# payload2.net
KiCad netlist of a schematic drawn in EAGLE
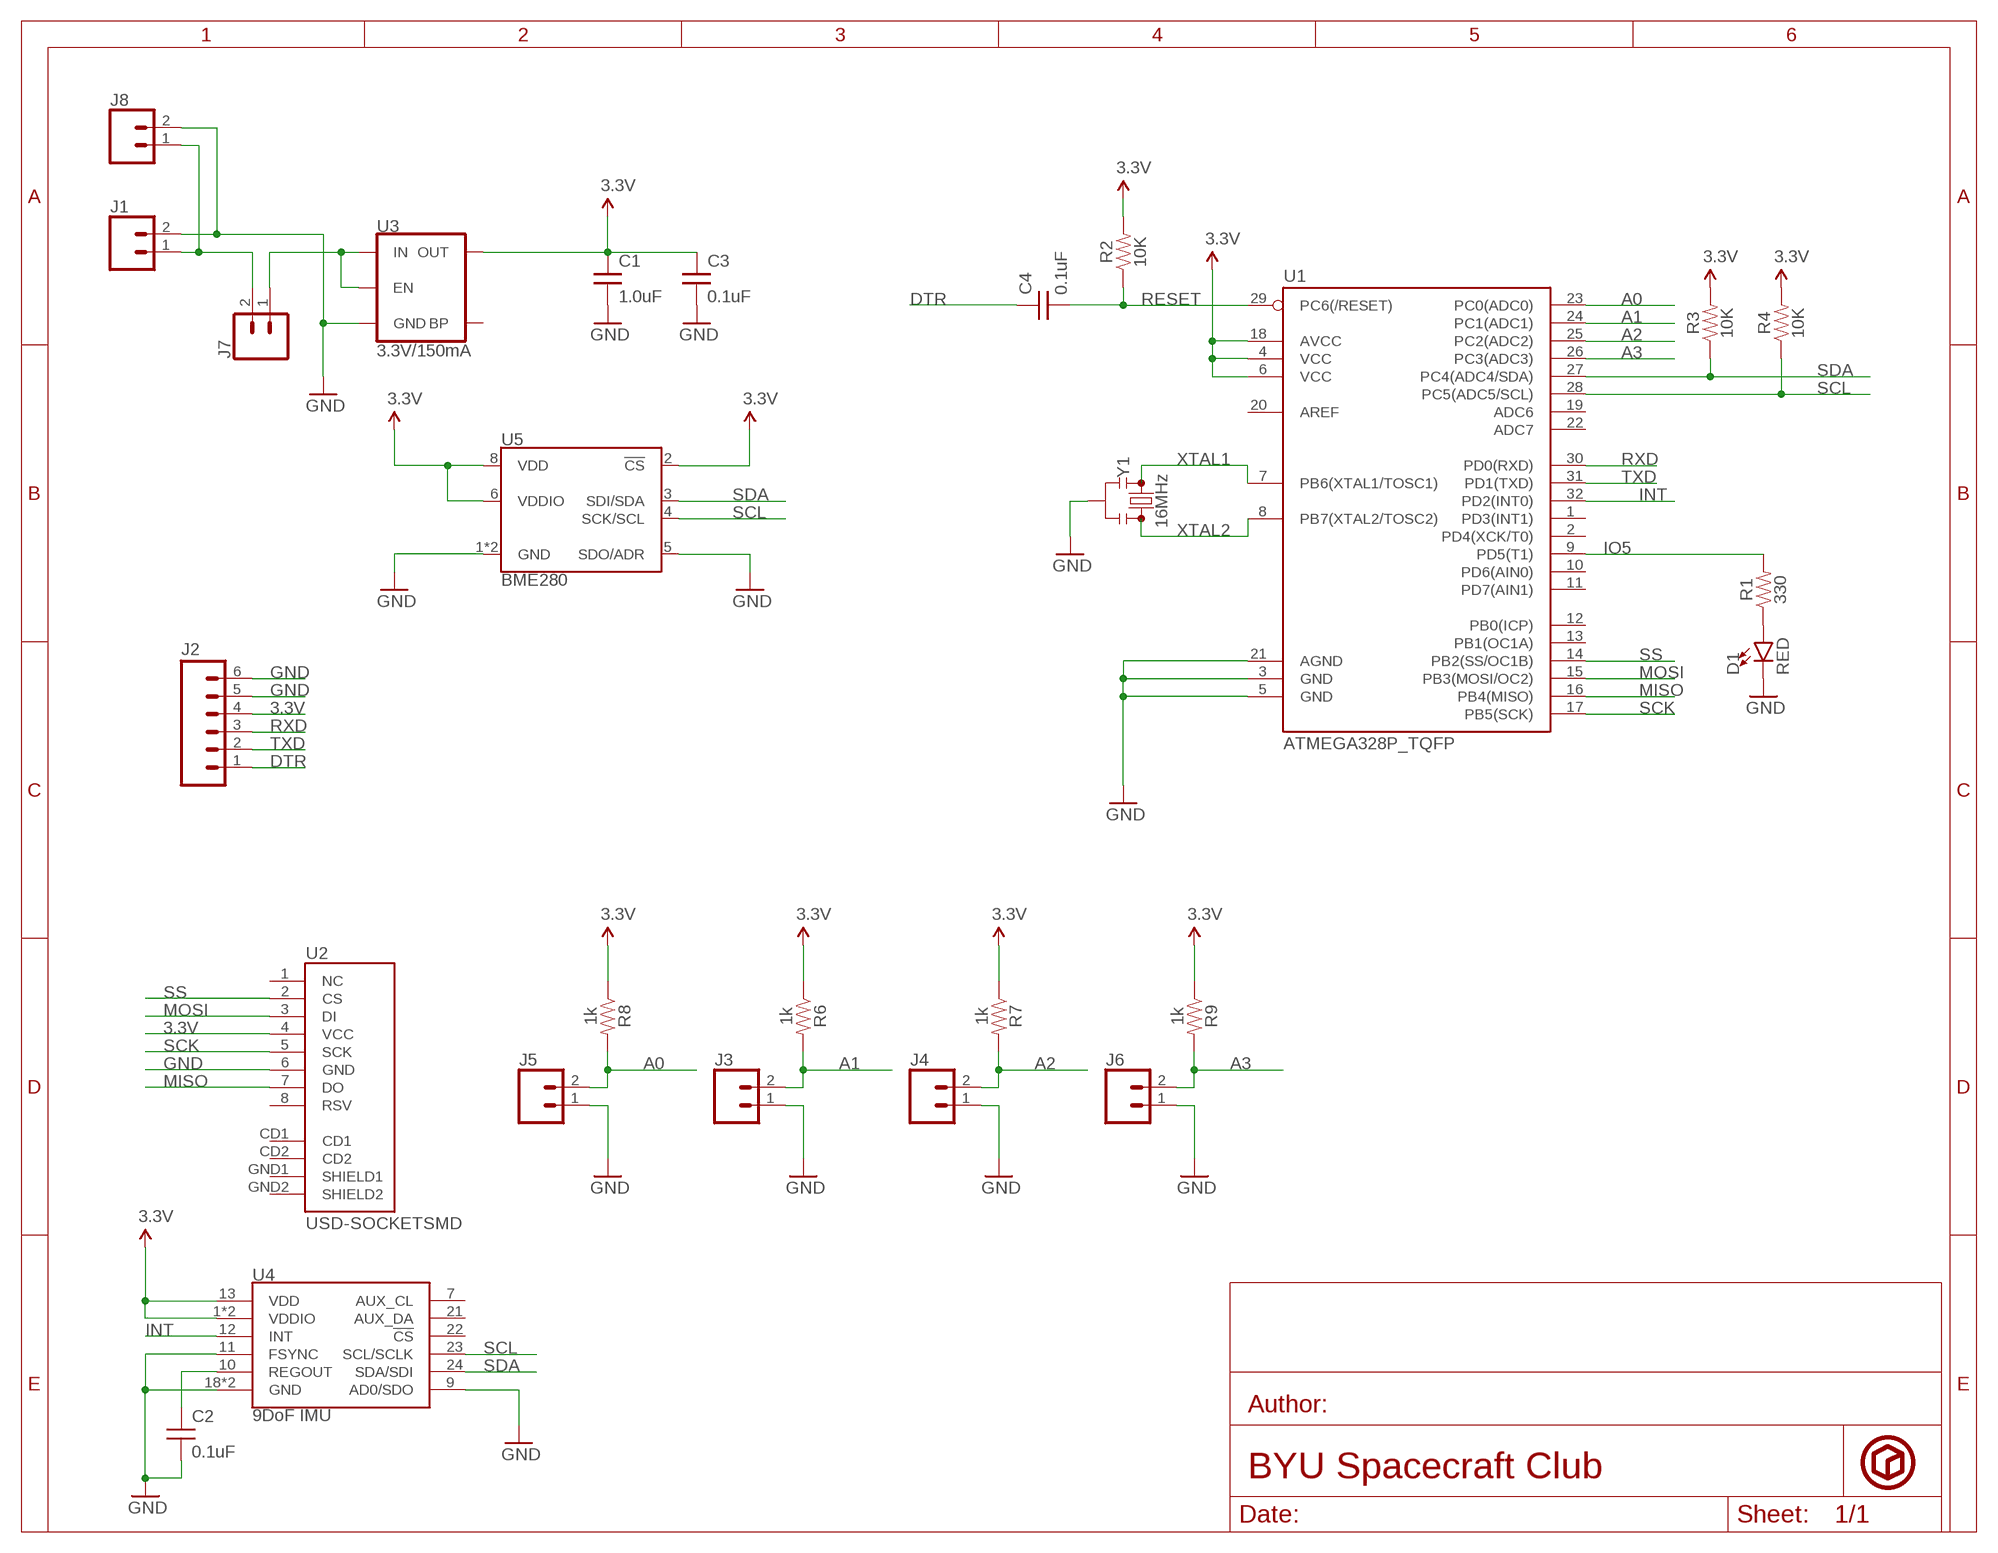
[diagram p0: schematic, sheet 1]

(export (version "E")
  (design (tool "Eeschema 10.0.6"))
  (components
    (comp (ref "C1")
      (value "1.0uF")
      (footprint "eagle-import:0603")
      (libsource (lib "eagle-import") (part "CAPACITOR_1.0UF-0603-16V-10%"))
    )
    (comp (ref "C2")
      (value "0.1uF")
      (footprint "eagle-import:0603-CAP")
      (libsource (lib "eagle-import") (part "CAPACITOR_0.1UF"))
    )
    (comp (ref "C3")
      (value "0.1uF")
      (footprint "eagle-import:0603-CAP")
      (libsource (lib "eagle-import") (part "CAPACITOR_0.1UF"))
    )
    (comp (ref "C4")
      (value "0.1uF")
      (footprint "eagle-import:0603-CAP")
      (libsource (lib "eagle-import") (part "CAPACITOR_0.1UF"))
    )
    (comp (ref "D1")
      (value "RED")
      (footprint "eagle-import:LED-0603")
      (libsource (lib "eagle-import") (part "LED_RED0603"))
    )
    (comp (ref "J1")
      (value "CONN_02")
      (footprint "eagle-import:1X02")
      (libsource (lib "eagle-import") (part "CONN_02"))
    )
    (comp (ref "J2")
      (value "CONNECTOR_6PINSILK_FEMALE_PTH")
      (footprint "eagle-import:1X06")
      (libsource (lib "eagle-import") (part "CONNECTOR_6PINSILK_FEMALE_PTH"))
    )
    (comp (ref "J3")
      (value "CONN_02")
      (footprint "eagle-import:1X02")
      (libsource (lib "eagle-import") (part "CONN_02"))
    )
    (comp (ref "J4")
      (value "CONN_02")
      (footprint "eagle-import:1X02")
      (libsource (lib "eagle-import") (part "CONN_02"))
    )
    (comp (ref "J5")
      (value "CONN_02")
      (footprint "eagle-import:1X02")
      (libsource (lib "eagle-import") (part "CONN_02"))
    )
    (comp (ref "J6")
      (value "CONN_02")
      (footprint "eagle-import:1X02")
      (libsource (lib "eagle-import") (part "CONN_02"))
    )
    (comp (ref "J7")
      (value "CONN_02")
      (footprint "eagle-import:1X02")
      (libsource (lib "eagle-import") (part "CONN_02"))
    )
    (comp (ref "J8")
      (value "CONN_02")
      (footprint "eagle-import:1X02")
      (libsource (lib "eagle-import") (part "CONN_02"))
    )
    (comp (ref "R1")
      (value "330")
      (footprint "eagle-import:0603")
      (libsource (lib "eagle-import") (part "RESISTOR_330OHM-0603-1/10W-1%"))
    )
    (comp (ref "R2")
      (value "10K")
      (footprint "eagle-import:0603-RES")
      (libsource (lib "eagle-import") (part "RESISTOR_10KOHM0603"))
    )
    (comp (ref "R3")
      (value "10K")
      (footprint "eagle-import:0603-RES")
      (libsource (lib "eagle-import") (part "RESISTOR_10KOHM0603"))
    )
    (comp (ref "R4")
      (value "10K")
      (footprint "eagle-import:0603-RES")
      (libsource (lib "eagle-import") (part "RESISTOR_10KOHM0603"))
    )
    (comp (ref "R6")
      (value "1k")
      (footprint "eagle-import:0603")
      (libsource (lib "eagle-import") (part "RESISTOR_1KOHM-0603-1/10W-5%"))
    )
    (comp (ref "R7")
      (value "1k")
      (footprint "eagle-import:0603")
      (libsource (lib "eagle-import") (part "RESISTOR_1KOHM-0603-1/10W-5%"))
    )
    (comp (ref "R8")
      (value "1k")
      (footprint "eagle-import:0603")
      (libsource (lib "eagle-import") (part "RESISTOR_1KOHM-0603-1/10W-5%"))
    )
    (comp (ref "R9")
      (value "1k")
      (footprint "eagle-import:0603")
      (libsource (lib "eagle-import") (part "RESISTOR_1KOHM-0603-1/10W-5%"))
    )
    (comp (ref "U1")
      (value "ATMEGA328P_TQFP")
      (footprint "eagle-import:TQFP32-08")
      (libsource (lib "eagle-import") (part "ATMEGA328P_TQFP"))
    )
    (comp (ref "U2")
      (value "USD-SOCKETSMD")
      (footprint "eagle-import:MICRO-SD-SOCKET-PP")
      (libsource (lib "eagle-import") (part "USD-SOCKETSMD"))
    )
    (comp (ref "U3")
      (value "3.3V/150mA")
      (footprint "eagle-import:SOT23-5")
      (libsource (lib "eagle-import") (part "VOLTAGE_REGULATOR_MIC52053.3V"))
    )
    (comp (ref "U4")
      (value "9DoF IMU")
      (footprint "eagle-import:QFN24-3X3")
      (libsource (lib "eagle-import") (part "MPU9250"))
    )
    (comp (ref "U5")
      (value "BME280")
      (footprint "eagle-import:LGA-8-2.5X2.5")
      (libsource (lib "eagle-import") (part "BME280"))
    )
    (comp (ref "Y1")
      (value "16MHz")
      (footprint "eagle-import:RESONATOR-SMD-3.2X1.3")
      (libsource (lib "eagle-import") (part "RESONATOR_16MHZSMD_3.2X1.3"))
    )
  )
  (nets
    (net (code "1") (name "/A0") (class "Default")
      (node (ref "J5") (pin "2") (pinfunction "2_2") (pintype "passive"))
      (node (ref "R8") (pin "2") (pinfunction "2_2") (pintype "passive"))
      (node (ref "U1") (pin "23") (pinfunction "PC0(ADC0)_23") (pintype "bidirectional"))
    )
    (net (code "2") (name "/A1") (class "Default")
      (node (ref "J3") (pin "2") (pinfunction "2_2") (pintype "passive"))
      (node (ref "R6") (pin "2") (pinfunction "2_2") (pintype "passive"))
      (node (ref "U1") (pin "24") (pinfunction "PC1(ADC1)_24") (pintype "bidirectional"))
    )
    (net (code "3") (name "/A2") (class "Default")
      (node (ref "J4") (pin "2") (pinfunction "2_2") (pintype "passive"))
      (node (ref "R7") (pin "2") (pinfunction "2_2") (pintype "passive"))
      (node (ref "U1") (pin "25") (pinfunction "PC2(ADC2)_25") (pintype "bidirectional"))
    )
    (net (code "4") (name "/A3") (class "Default")
      (node (ref "J6") (pin "2") (pinfunction "2_2") (pintype "passive"))
      (node (ref "R9") (pin "2") (pinfunction "2_2") (pintype "passive"))
      (node (ref "U1") (pin "26") (pinfunction "PC3(ADC3)_26") (pintype "bidirectional"))
    )
    (net (code "5") (name "/DTR") (class "Default")
      (node (ref "C4") (pin "1") (pinfunction "1_1") (pintype "passive"))
      (node (ref "J2") (pin "1") (pinfunction "1_1") (pintype "passive"))
    )
    (net (code "6") (name "/INT") (class "Default")
      (node (ref "U1") (pin "32") (pinfunction "PD2(INT0)_32") (pintype "bidirectional"))
      (node (ref "U4") (pin "12") (pinfunction "INT_12") (pintype "bidirectional"))
    )
    (net (code "7") (name "/IO5") (class "Default")
      (node (ref "R1") (pin "2") (pinfunction "2_2") (pintype "passive"))
      (node (ref "U1") (pin "9") (pinfunction "PD5(T1)_9") (pintype "bidirectional"))
    )
    (net (code "8") (name "/MISO") (class "Default")
      (node (ref "U1") (pin "16") (pinfunction "PB4(MISO)_16") (pintype "bidirectional"))
      (node (ref "U2") (pin "7") (pinfunction "DO_7") (pintype "bidirectional"))
    )
    (net (code "9") (name "/MOSI") (class "Default")
      (node (ref "U1") (pin "15") (pinfunction "PB3(MOSI/OC2)_15") (pintype "bidirectional"))
      (node (ref "U2") (pin "3") (pinfunction "DI_3") (pintype "bidirectional"))
    )
    (net (code "10") (name "/RESET") (class "Default")
      (node (ref "C4") (pin "2") (pinfunction "2_2") (pintype "passive"))
      (node (ref "R2") (pin "1") (pinfunction "1_1") (pintype "passive"))
      (node (ref "U1") (pin "29") (pinfunction "PC6(/RESET)_29") (pintype "bidirectional"))
    )
    (net (code "11") (name "/RXD") (class "Default")
      (node (ref "J2") (pin "3") (pinfunction "3_3") (pintype "passive"))
      (node (ref "U1") (pin "30") (pinfunction "PD0(RXD)_30") (pintype "bidirectional"))
    )
    (net (code "12") (name "/SCK") (class "Default")
      (node (ref "U1") (pin "17") (pinfunction "PB5(SCK)_17") (pintype "bidirectional"))
      (node (ref "U2") (pin "5") (pinfunction "SCK_5") (pintype "bidirectional"))
    )
    (net (code "13") (name "/SCL") (class "Default")
      (node (ref "R4") (pin "1") (pinfunction "1_1") (pintype "passive"))
      (node (ref "U1") (pin "28") (pinfunction "PC5(ADC5/SCL)_28") (pintype "bidirectional"))
      (node (ref "U4") (pin "23") (pinfunction "SCL/SCLK_23") (pintype "bidirectional"))
      (node (ref "U5") (pin "4") (pinfunction "SCK/SCL_4") (pintype "bidirectional"))
    )
    (net (code "14") (name "/SDA") (class "Default")
      (node (ref "R3") (pin "1") (pinfunction "1_1") (pintype "passive"))
      (node (ref "U1") (pin "27") (pinfunction "PC4(ADC4/SDA)_27") (pintype "bidirectional"))
      (node (ref "U4") (pin "24") (pinfunction "SDA/SDI_24") (pintype "bidirectional"))
      (node (ref "U5") (pin "3") (pinfunction "SDI/SDA_3") (pintype "bidirectional"))
    )
    (net (code "15") (name "/SS") (class "Default")
      (node (ref "U1") (pin "14") (pinfunction "PB2(SS/OC1B)_14") (pintype "bidirectional"))
      (node (ref "U2") (pin "2") (pinfunction "CS_2") (pintype "bidirectional"))
    )
    (net (code "16") (name "/TXD") (class "Default")
      (node (ref "J2") (pin "2") (pinfunction "2_2") (pintype "passive"))
      (node (ref "U1") (pin "31") (pinfunction "PD1(TXD)_31") (pintype "bidirectional"))
    )
    (net (code "17") (name "/XTAL1") (class "Default")
      (node (ref "U1") (pin "7") (pinfunction "PB6(XTAL1/TOSC1)_7") (pintype "bidirectional"))
      (node (ref "Y1") (pin "1") (pinfunction "1_1") (pintype "passive"))
    )
    (net (code "18") (name "/XTAL2") (class "Default")
      (node (ref "U1") (pin "8") (pinfunction "PB7(XTAL2/TOSC2)_8") (pintype "bidirectional"))
      (node (ref "Y1") (pin "3") (pinfunction "3_3") (pintype "passive"))
    )
    (net (code "19") (name "3.3V") (class "Default")
      (node (ref "C1") (pin "1") (pinfunction "1_1") (pintype "passive"))
      (node (ref "C3") (pin "1") (pinfunction "1_1") (pintype "passive"))
      (node (ref "J2") (pin "4") (pinfunction "4_4") (pintype "passive"))
      (node (ref "R2") (pin "2") (pinfunction "2_2") (pintype "passive"))
      (node (ref "R3") (pin "2") (pinfunction "2_2") (pintype "passive"))
      (node (ref "R4") (pin "2") (pinfunction "2_2") (pintype "passive"))
      (node (ref "R6") (pin "1") (pinfunction "1_1") (pintype "passive"))
      (node (ref "R7") (pin "1") (pinfunction "1_1") (pintype "passive"))
      (node (ref "R8") (pin "1") (pinfunction "1_1") (pintype "passive"))
      (node (ref "R9") (pin "1") (pinfunction "1_1") (pintype "passive"))
      (node (ref "U1") (pin "18") (pinfunction "AVCC_18") (pintype "bidirectional"))
      (node (ref "U1") (pin "4") (pinfunction "VCC_4") (pintype "bidirectional"))
      (node (ref "U1") (pin "6") (pinfunction "VCC_6") (pintype "bidirectional"))
      (node (ref "U2") (pin "4") (pinfunction "VCC_4") (pintype "bidirectional"))
      (node (ref "U3") (pin "5") (pinfunction "OUT_5") (pintype "passive"))
      (node (ref "U4") (pin "1") (pinfunction "VDDIO_1") (pintype "bidirectional"))
      (node (ref "U4") (pin "13") (pinfunction "VDD_13") (pintype "bidirectional"))
      (node (ref "U4") (pin "8") (pinfunction "VDDIO_8") (pintype "bidirectional"))
      (node (ref "U5") (pin "2") (pinfunction "~{CS}_2") (pintype "bidirectional"))
      (node (ref "U5") (pin "6") (pinfunction "VDDIO_6") (pintype "bidirectional"))
      (node (ref "U5") (pin "8") (pinfunction "VDD_8") (pintype "bidirectional"))
    )
    (net (code "20") (name "GND") (class "Default")
      (node (ref "C1") (pin "2") (pinfunction "2_2") (pintype "passive"))
      (node (ref "C2") (pin "2") (pinfunction "2_2") (pintype "passive"))
      (node (ref "C3") (pin "2") (pinfunction "2_2") (pintype "passive"))
      (node (ref "D1") (pin "C") (pinfunction "C_C") (pintype "passive"))
      (node (ref "J1") (pin "2") (pinfunction "2_2") (pintype "passive"))
      (node (ref "J2") (pin "5") (pinfunction "5_5") (pintype "passive"))
      (node (ref "J2") (pin "6") (pinfunction "6_6") (pintype "passive"))
      (node (ref "J3") (pin "1") (pinfunction "1_1") (pintype "passive"))
      (node (ref "J4") (pin "1") (pinfunction "1_1") (pintype "passive"))
      (node (ref "J5") (pin "1") (pinfunction "1_1") (pintype "passive"))
      (node (ref "J6") (pin "1") (pinfunction "1_1") (pintype "passive"))
      (node (ref "J8") (pin "2") (pinfunction "2_2") (pintype "passive"))
      (node (ref "U1") (pin "21") (pinfunction "AGND_21") (pintype "bidirectional"))
      (node (ref "U1") (pin "3") (pinfunction "GND_3") (pintype "bidirectional"))
      (node (ref "U1") (pin "5") (pinfunction "GND_5") (pintype "bidirectional"))
      (node (ref "U2") (pin "6") (pinfunction "GND_6") (pintype "bidirectional"))
      (node (ref "U3") (pin "2") (pinfunction "GND_2") (pintype "input"))
      (node (ref "U4") (pin "11") (pinfunction "FSYNC_11") (pintype "bidirectional"))
      (node (ref "U4") (pin "18") (pinfunction "GND_18") (pintype "bidirectional"))
      (node (ref "U4") (pin "20") (pinfunction "GND_20") (pintype "bidirectional"))
      (node (ref "U4") (pin "9") (pinfunction "AD0/SDO_9") (pintype "bidirectional"))
      (node (ref "U5") (pin "1") (pinfunction "GND_1") (pintype "bidirectional"))
      (node (ref "U5") (pin "5") (pinfunction "SDO/ADR_5") (pintype "bidirectional"))
      (node (ref "U5") (pin "7") (pinfunction "GND_7") (pintype "bidirectional"))
      (node (ref "Y1") (pin "2") (pinfunction "2_2") (pintype "passive"))
    )
    (net (code "21") (name "Net-(D1-PadA)") (class "Default")
      (node (ref "D1") (pin "A") (pinfunction "A_A") (pintype "passive"))
      (node (ref "R1") (pin "1") (pinfunction "1_1") (pintype "passive"))
    )
    (net (code "22") (name "Net-(J1-Pad1)") (class "Default")
      (node (ref "J1") (pin "1") (pinfunction "1_1") (pintype "passive"))
      (node (ref "J7") (pin "2") (pinfunction "2_2") (pintype "passive"))
      (node (ref "J8") (pin "1") (pinfunction "1_1") (pintype "passive"))
    )
    (net (code "23") (name "Net-(U3-EN)") (class "Default")
      (node (ref "J7") (pin "1") (pinfunction "1_1") (pintype "passive"))
      (node (ref "U3") (pin "1") (pinfunction "IN_1") (pintype "input"))
      (node (ref "U3") (pin "3") (pinfunction "EN_3") (pintype "input"))
    )
    (net (code "24") (name "Net-(U4-REGOUT)") (class "Default")
      (node (ref "C2") (pin "1") (pinfunction "1_1") (pintype "passive"))
      (node (ref "U4") (pin "10") (pinfunction "REGOUT_10") (pintype "bidirectional"))
    )
    (net (code "25") (name "unconnected-(U1-ADC6-Pad19)") (class "Default")
      (node (ref "U1") (pin "19") (pinfunction "ADC6_19") (pintype "bidirectional"))
    )
    (net (code "26") (name "unconnected-(U1-ADC7-Pad22)") (class "Default")
      (node (ref "U1") (pin "22") (pinfunction "ADC7_22") (pintype "bidirectional"))
    )
    (net (code "27") (name "unconnected-(U1-AREF-Pad20)") (class "Default")
      (node (ref "U1") (pin "20") (pinfunction "AREF_20") (pintype "bidirectional"))
    )
    (net (code "28") (name "unconnected-(U1-PB0(ICP)-Pad12)") (class "Default")
      (node (ref "U1") (pin "12") (pinfunction "PB0(ICP)_12") (pintype "bidirectional"))
    )
    (net (code "29") (name "unconnected-(U1-PB1(OC1A)-Pad13)") (class "Default")
      (node (ref "U1") (pin "13") (pinfunction "PB1(OC1A)_13") (pintype "bidirectional"))
    )
    (net (code "30") (name "unconnected-(U1-PD3(INT1)-Pad1)") (class "Default")
      (node (ref "U1") (pin "1") (pinfunction "PD3(INT1)_1") (pintype "bidirectional"))
    )
    (net (code "31") (name "unconnected-(U1-PD4(XCK{slash}T0)-Pad2)") (class "Default")
      (node (ref "U1") (pin "2") (pinfunction "PD4(XCK/T0)_2") (pintype "bidirectional"))
    )
    (net (code "32") (name "unconnected-(U1-PD6(AIN0)-Pad10)") (class "Default")
      (node (ref "U1") (pin "10") (pinfunction "PD6(AIN0)_10") (pintype "bidirectional"))
    )
    (net (code "33") (name "unconnected-(U1-PD7(AIN1)-Pad11)") (class "Default")
      (node (ref "U1") (pin "11") (pinfunction "PD7(AIN1)_11") (pintype "bidirectional"))
    )
    (net (code "34") (name "unconnected-(U2-NC-Pad1)") (class "Default")
      (node (ref "U2") (pin "1") (pinfunction "NC_1") (pintype "bidirectional"))
    )
    (net (code "35") (name "unconnected-(U2-PadCD1)") (class "Default")
      (node (ref "U2") (pin "CD1") (pinfunction "CD1_CD1") (pintype "bidirectional"))
    )
    (net (code "36") (name "unconnected-(U2-PadCD2)") (class "Default")
      (node (ref "U2") (pin "CD2") (pinfunction "CD2_CD2") (pintype "bidirectional"))
    )
    (net (code "37") (name "unconnected-(U2-RSV-Pad8)") (class "Default")
      (node (ref "U2") (pin "8") (pinfunction "RSV_8") (pintype "bidirectional"))
    )
    (net (code "38") (name "unconnected-(U2-SHIELD1-PadGND1)") (class "Default")
      (node (ref "U2") (pin "GND1") (pinfunction "SHIELD1_GND1") (pintype "bidirectional"))
    )
    (net (code "39") (name "unconnected-(U2-SHIELD2-PadGND2)") (class "Default")
      (node (ref "U2") (pin "GND2") (pinfunction "SHIELD2_GND2") (pintype "bidirectional"))
    )
    (net (code "40") (name "unconnected-(U3-BP-Pad4)") (class "Default")
      (node (ref "U3") (pin "4") (pinfunction "BP_4") (pintype "input"))
    )
    (net (code "41") (name "unconnected-(U4-AUX_CL-Pad7)") (class "Default")
      (node (ref "U4") (pin "7") (pinfunction "AUX_CL_7") (pintype "bidirectional"))
    )
    (net (code "42") (name "unconnected-(U4-AUX_DA-Pad21)") (class "Default")
      (node (ref "U4") (pin "21") (pinfunction "AUX_DA_21") (pintype "bidirectional"))
    )
    (net (code "43") (name "unconnected-(U4-~{CS}-Pad22)") (class "Default")
      (node (ref "U4") (pin "22") (pinfunction "~{CS}_22") (pintype "bidirectional"))
    )
  )
)
